# Sheet1.net
KiCad netlist of a schematic drawn in Altium Designer
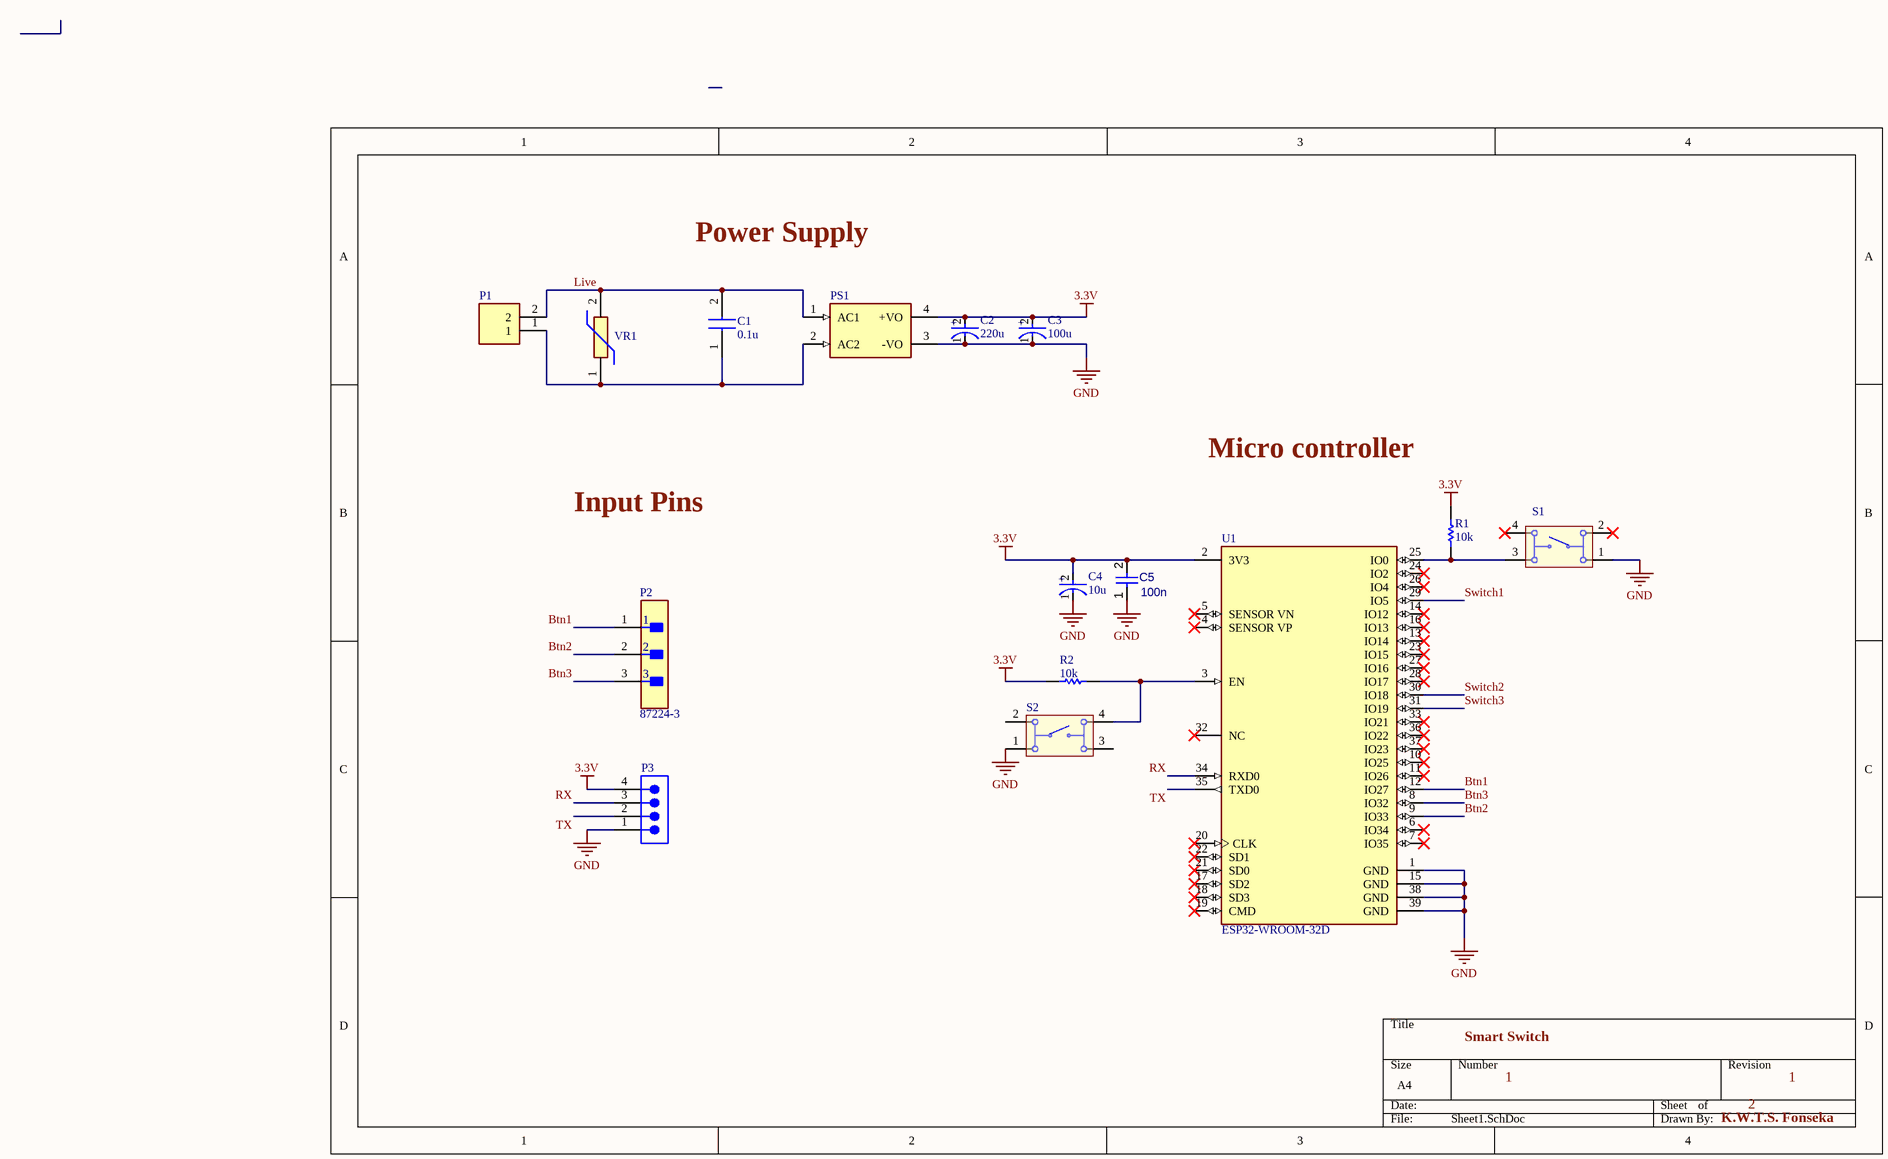
[diagram p0: Sheet1.SchDoc]

(export (version "E")
  (design (tool "Eeschema 10.0.6"))
  (components
    (comp (ref "C1")
      (value "0.1u")
      (footprint "SamacSys:B32922X_(18_X_5)")
      (description "Safety Capacitor")
      (fields
        (field (name "MANUFACTURER_PART_NUMBER") "B32922X2104K000")
        (field (name "MOUSER PART NUMBER") "871-B32922X2104K000")
      )
      (libsource (lib "*") (part "B32922X2104K000"))
    )
    (comp (ref "C2")
      (value "220u")
      (footprint "FP-RAD-TH-D_6_3_0_5-L_11-MFG")
      (description "Aluminum Electrolytic Capacitors (Radial Lead Type) 220uF ±20% 10V")
      (fields (field (name "VOLTAGE") "10V") (field (name "TOLERANCE") "20%"))
      (libsource (lib "Altium Content Vault") (part "a00bbbee19879c290e62620ae7e47b1"))
    )
    (comp (ref "C3")
      (value "100u")
      (footprint "FP-UKL1A101KED1TD-MFG")
      (description "CAP ALUM 100UF 10% 10V RADIAL")
      (fields (field (name "TOLERANCE") "10%") (field (name "MANUFACTURER") "Nichicon"))
      (libsource (lib "Altium Content Vault") (part "203bc49f2ac43e59fd269a8c329ed05"))
    )
    (comp (ref "C4")
      (value "10u")
      (footprint "FP-T491A106M010AT-MFG")
      (description "CAP TANT 10UF 20% 10V 1206")
      (fields (field (name "VOLTAGE") "10V") (field (name "TOLERANCE") "20%"))
      (libsource (lib "Altium Content Vault") (part "a00bbbee19879c290e62620ae7e47b1"))
    )
    (comp (ref "C5")
      (value "100n")
      (footprint "CAPC2013X95X50LL10T25")
      (description "Chip Capacitor, 100 nF, +/- 10%, 50 V, 0805 (2012 Metric)")
      (fields (field (name "TOLERANCE") "10%"))
      (libsource (lib "Tharusha Fonseka- UoM") (part "CAP-NP-2"))
    )
    (comp (ref "P1")
      (value "282841-2")
      (footprint "TE_282841-2")
      (description "Conn Terminal Block 2 POS 5.08mm Solder ST Thru-Hole 17.5A/Contact")
      (fields (field (name "MF") "TE Connectivity"))
      (libsource (lib "Tharusha Fonseka- UoM") (part "282841-2"))
    )
    (comp (ref "P2")
      (value "87224-3")
      (footprint "FP-87224-3-MFG")
      (description "CONN HEADER VERT 3POS 2.54MM")
      (libsource (lib "Altium Content Vault") (part "0d3f023dd272f625e17a2be33dea85f"))
    )
    (comp (ref "P3")
      (value "TSW-104-08-L-S")
      (footprint "SMTC-TSW-104-08-X-S")
      (description "0.025\" SQ Post Header, Through-hole, Vertical, -55 to 125 degC, 2.54 mm Pitch, 4-Pin, Male, RoHS")
      (fields (field (name "MANUFACTURER") "Samtec"))
      (libsource (lib "Altium Content Vault") (part "SMTC-TSW-104-08-X-S"))
    )
    (comp (ref "PS1")
      (value "HLK-PM03")
      (footprint "CONV_HLK-PM03")
      (fields (field (name "MF") "Hi-link"))
      (libsource (lib "Tharusha Fonseka- UoM") (part "HLK-PM03"))
    )
    (comp (ref "R1")
      (value "10k")
      (footprint "RESC2013X70X40ML20T20")
      (description "ERJ-6ENF1002V")
      (fields (field (name "MANUFACTURER") "Panasonic"))
      (libsource (lib "Altium Content Vault") (part "RES"))
    )
    (comp (ref "R2")
      (value "10k")
      (footprint "RESC2013X70X40ML20T20")
      (description "ERJ-6ENF1002V")
      (fields (field (name "MANUFACTURER") "Panasonic"))
      (libsource (lib "Altium Content Vault") (part "RES"))
    )
    (comp (ref "S1")
      (value "430471025826")
      (footprint "430471025826")
      (description "WS-TASV SMD Tact Switch 6X6 mm")
      (fields (field (name "MANUFACTURER") "Wuerth Elektronik"))
      (libsource (lib "") (part "WE-TACT-SW-4_A_1"))
    )
    (comp (ref "S2")
      (value "430471025826")
      (footprint "430471025826")
      (description "WS-TASV SMD Tact Switch 6X6 mm")
      (fields (field (name "MANUFACTURER") "Wuerth Elektronik"))
      (libsource (lib "Altium Content Vault") (part "WE-TACT-SW-4_A"))
    )
    (comp (ref "U1")
      (value "ESP32-WROOM-32D")
      (footprint "FP-ESP32-WROOM-32D-MFG")
      (description "WIFI MODULE 32MBITS SPI FLASH")
      (fields
        (field (name "OCTOPART") "https://octopart.com/esp32-wroom-32d-espressif+systems-91040050")
        (field (name "MANUFACTURER") "Espressif Systems")
      )
      (libsource (lib "Altium Content Vault") (part "a031a76f8c27026a7a7f4657ff233a3"))
    )
    (comp (ref "VR1")
      (value "MOV-10D561K")
      (footprint "SamacSys:MOV10D561K")
      (description "Varistor")
      (fields (field (name "MOUSER PART NUMBER") "652-MOV-10D561K"))
      (libsource (lib "*") (part "MOV-10D561K"))
    )
  )
  (nets
    (net (code "1") (name "/Btn1") (class "Default")
      (node (ref "P2") (pin "1") (pinfunction "1_1") (pintype "passive"))
      (node (ref "U1") (pin "12") (pinfunction "IO27_12") (pintype "bidirectional"))
    )
    (net (code "2") (name "/Btn2") (class "Default")
      (node (ref "P2") (pin "2") (pinfunction "2_2") (pintype "passive"))
      (node (ref "U1") (pin "9") (pinfunction "IO33_9") (pintype "bidirectional"))
    )
    (net (code "3") (name "/Btn3") (class "Default")
      (node (ref "P2") (pin "3") (pinfunction "3_3") (pintype "passive"))
      (node (ref "U1") (pin "8") (pinfunction "IO32_8") (pintype "bidirectional"))
    )
    (net (code "4") (name "/Live") (class "Default")
      (node (ref "C1") (pin "2") (pinfunction "2_2") (pintype "passive"))
      (node (ref "P1") (pin "2") (pinfunction "2_2") (pintype "passive"))
      (node (ref "PS1") (pin "1") (pinfunction "AC1_1") (pintype "input"))
      (node (ref "VR1") (pin "2") (pinfunction "2_2") (pintype "passive"))
    )
    (net (code "5") (name "/RX") (class "Default")
      (node (ref "P3") (pin "3") (pinfunction "3_3") (pintype "passive"))
      (node (ref "U1") (pin "34") (pinfunction "RXD0_34") (pintype "input"))
    )
    (net (code "6") (name "/Switch1") (class "Default")
      (node (ref "U1") (pin "29") (pinfunction "IO5_29") (pintype "bidirectional"))
    )
    (net (code "7") (name "/Switch2") (class "Default")
      (node (ref "U1") (pin "30") (pinfunction "IO18_30") (pintype "bidirectional"))
    )
    (net (code "8") (name "/Switch3") (class "Default")
      (node (ref "U1") (pin "31") (pinfunction "IO19_31") (pintype "bidirectional"))
    )
    (net (code "9") (name "/TX") (class "Default")
      (node (ref "P3") (pin "2") (pinfunction "2_2") (pintype "passive"))
      (node (ref "U1") (pin "35") (pinfunction "TXD0_35") (pintype "output"))
    )
    (net (code "10") (name "3.3V") (class "Default")
      (node (ref "C2") (pin "2") (pinfunction "A_2") (pintype "passive"))
      (node (ref "C3") (pin "2") (pinfunction "A_2") (pintype "passive"))
      (node (ref "C4") (pin "2") (pinfunction "A_2") (pintype "passive"))
      (node (ref "C5") (pin "2") (pinfunction "2_2") (pintype "passive"))
      (node (ref "P3") (pin "4") (pinfunction "4_4") (pintype "passive"))
      (node (ref "PS1") (pin "4") (pinfunction "+VO_4") (pintype "power_in"))
      (node (ref "R1") (pin "2") (pinfunction "2_2") (pintype "passive"))
      (node (ref "R2") (pin "1") (pinfunction "1_1") (pintype "passive"))
      (node (ref "U1") (pin "2") (pinfunction "3V3_2") (pintype "power_in"))
    )
    (net (code "11") (name "GND") (class "Default")
      (node (ref "C2") (pin "1") (pinfunction "C_1") (pintype "passive"))
      (node (ref "C3") (pin "1") (pinfunction "C_1") (pintype "passive"))
      (node (ref "C4") (pin "1") (pinfunction "C_1") (pintype "passive"))
      (node (ref "C5") (pin "1") (pinfunction "1_1") (pintype "passive"))
      (node (ref "P3") (pin "1") (pinfunction "1_1") (pintype "passive"))
      (node (ref "PS1") (pin "3") (pinfunction "-VO_3") (pintype "power_in"))
      (node (ref "S1") (pin "1") (pinfunction "1_1") (pintype "passive"))
      (node (ref "S2") (pin "1") (pinfunction "1_1") (pintype "passive"))
      (node (ref "U1") (pin "1") (pinfunction "GND_1") (pintype "power_in"))
      (node (ref "U1") (pin "15") (pinfunction "GND_15") (pintype "power_in"))
      (node (ref "U1") (pin "38") (pinfunction "GND_38") (pintype "power_in"))
      (node (ref "U1") (pin "39") (pinfunction "GND_39") (pintype "power_in"))
    )
    (net (code "12") (name "Net-(PS1-AC2)") (class "Default")
      (node (ref "C1") (pin "1") (pinfunction "1_1") (pintype "passive"))
      (node (ref "P1") (pin "1") (pinfunction "1_1") (pintype "passive"))
      (node (ref "PS1") (pin "2") (pinfunction "AC2_2") (pintype "input"))
      (node (ref "VR1") (pin "1") (pinfunction "1_1") (pintype "passive"))
    )
    (net (code "13") (name "Net-(U1-EN)") (class "Default")
      (node (ref "R2") (pin "2") (pinfunction "2_2") (pintype "passive"))
      (node (ref "S2") (pin "4") (pinfunction "4_4") (pintype "passive"))
      (node (ref "U1") (pin "3") (pinfunction "EN_3") (pintype "input"))
    )
    (net (code "14") (name "Net-(U1-IO0)") (class "Default")
      (node (ref "R1") (pin "1") (pinfunction "1_1") (pintype "passive"))
      (node (ref "S1") (pin "3") (pinfunction "3_3") (pintype "passive"))
      (node (ref "U1") (pin "25") (pinfunction "IO0_25") (pintype "bidirectional"))
    )
    (net (code "15") (name "unconnected-(S1-Pad2)") (class "Default")
      (node (ref "S1") (pin "2") (pinfunction "2_2") (pintype "passive+no_connect"))
    )
    (net (code "16") (name "unconnected-(S1-Pad4)") (class "Default")
      (node (ref "S1") (pin "4") (pinfunction "4_4") (pintype "passive+no_connect"))
    )
    (net (code "17") (name "unconnected-(S2-Pad2)") (class "Default")
      (node (ref "S2") (pin "2") (pinfunction "2_2") (pintype "passive"))
    )
    (net (code "18") (name "unconnected-(S2-Pad3)") (class "Default")
      (node (ref "S2") (pin "3") (pinfunction "3_3") (pintype "passive"))
    )
    (net (code "19") (name "unconnected-(U1-CLK-Pad20)") (class "Default")
      (node (ref "U1") (pin "20") (pinfunction "CLK_20") (pintype "input+no_connect"))
    )
    (net (code "20") (name "unconnected-(U1-CMD-Pad19)") (class "Default")
      (node (ref "U1") (pin "19") (pinfunction "CMD_19") (pintype "bidirectional+no_connect"))
    )
    (net (code "21") (name "unconnected-(U1-IO2-Pad24)") (class "Default")
      (node (ref "U1") (pin "24") (pinfunction "IO2_24") (pintype "bidirectional+no_connect"))
    )
    (net (code "22") (name "unconnected-(U1-IO4-Pad26)") (class "Default")
      (node (ref "U1") (pin "26") (pinfunction "IO4_26") (pintype "bidirectional+no_connect"))
    )
    (net (code "23") (name "unconnected-(U1-IO12-Pad14)") (class "Default")
      (node (ref "U1") (pin "14") (pinfunction "IO12_14") (pintype "bidirectional+no_connect"))
    )
    (net (code "24") (name "unconnected-(U1-IO13-Pad16)") (class "Default")
      (node (ref "U1") (pin "16") (pinfunction "IO13_16") (pintype "bidirectional+no_connect"))
    )
    (net (code "25") (name "unconnected-(U1-IO14-Pad13)") (class "Default")
      (node (ref "U1") (pin "13") (pinfunction "IO14_13") (pintype "bidirectional+no_connect"))
    )
    (net (code "26") (name "unconnected-(U1-IO15-Pad23)") (class "Default")
      (node (ref "U1") (pin "23") (pinfunction "IO15_23") (pintype "bidirectional+no_connect"))
    )
    (net (code "27") (name "unconnected-(U1-IO16-Pad27)") (class "Default")
      (node (ref "U1") (pin "27") (pinfunction "IO16_27") (pintype "bidirectional+no_connect"))
    )
    (net (code "28") (name "unconnected-(U1-IO17-Pad28)") (class "Default")
      (node (ref "U1") (pin "28") (pinfunction "IO17_28") (pintype "bidirectional+no_connect"))
    )
    (net (code "29") (name "unconnected-(U1-IO21-Pad33)") (class "Default")
      (node (ref "U1") (pin "33") (pinfunction "IO21_33") (pintype "bidirectional+no_connect"))
    )
    (net (code "30") (name "unconnected-(U1-IO22-Pad36)") (class "Default")
      (node (ref "U1") (pin "36") (pinfunction "IO22_36") (pintype "bidirectional+no_connect"))
    )
    (net (code "31") (name "unconnected-(U1-IO23-Pad37)") (class "Default")
      (node (ref "U1") (pin "37") (pinfunction "IO23_37") (pintype "bidirectional+no_connect"))
    )
    (net (code "32") (name "unconnected-(U1-IO25-Pad10)") (class "Default")
      (node (ref "U1") (pin "10") (pinfunction "IO25_10") (pintype "bidirectional+no_connect"))
    )
    (net (code "33") (name "unconnected-(U1-IO26-Pad11)") (class "Default")
      (node (ref "U1") (pin "11") (pinfunction "IO26_11") (pintype "bidirectional+no_connect"))
    )
    (net (code "34") (name "unconnected-(U1-IO34-Pad6)") (class "Default")
      (node (ref "U1") (pin "6") (pinfunction "IO34_6") (pintype "bidirectional+no_connect"))
    )
    (net (code "35") (name "unconnected-(U1-IO35-Pad7)") (class "Default")
      (node (ref "U1") (pin "7") (pinfunction "IO35_7") (pintype "bidirectional+no_connect"))
    )
    (net (code "36") (name "unconnected-(U1-NC-Pad32)") (class "Default")
      (node (ref "U1") (pin "32") (pinfunction "NC_32") (pintype "passive+no_connect"))
    )
    (net (code "37") (name "unconnected-(U1-SD0-Pad21)") (class "Default")
      (node (ref "U1") (pin "21") (pinfunction "SD0_21") (pintype "bidirectional+no_connect"))
    )
    (net (code "38") (name "unconnected-(U1-SD1-Pad22)") (class "Default")
      (node (ref "U1") (pin "22") (pinfunction "SD1_22") (pintype "bidirectional+no_connect"))
    )
    (net (code "39") (name "unconnected-(U1-SD2-Pad17)") (class "Default")
      (node (ref "U1") (pin "17") (pinfunction "SD2_17") (pintype "bidirectional+no_connect"))
    )
    (net (code "40") (name "unconnected-(U1-SD3-Pad18)") (class "Default")
      (node (ref "U1") (pin "18") (pinfunction "SD3_18") (pintype "bidirectional+no_connect"))
    )
    (net (code "41") (name "unconnected-(U1-SENSOR_VN-Pad5)") (class "Default")
      (node (ref "U1") (pin "5") (pinfunction "SENSOR_VN_5") (pintype "bidirectional+no_connect"))
    )
    (net (code "42") (name "unconnected-(U1-SENSOR_VP-Pad4)") (class "Default")
      (node (ref "U1") (pin "4") (pinfunction "SENSOR_VP_4") (pintype "bidirectional+no_connect"))
    )
  )
)
